# BDL_Eagle.net
KiCad netlist of a schematic drawn in EAGLE
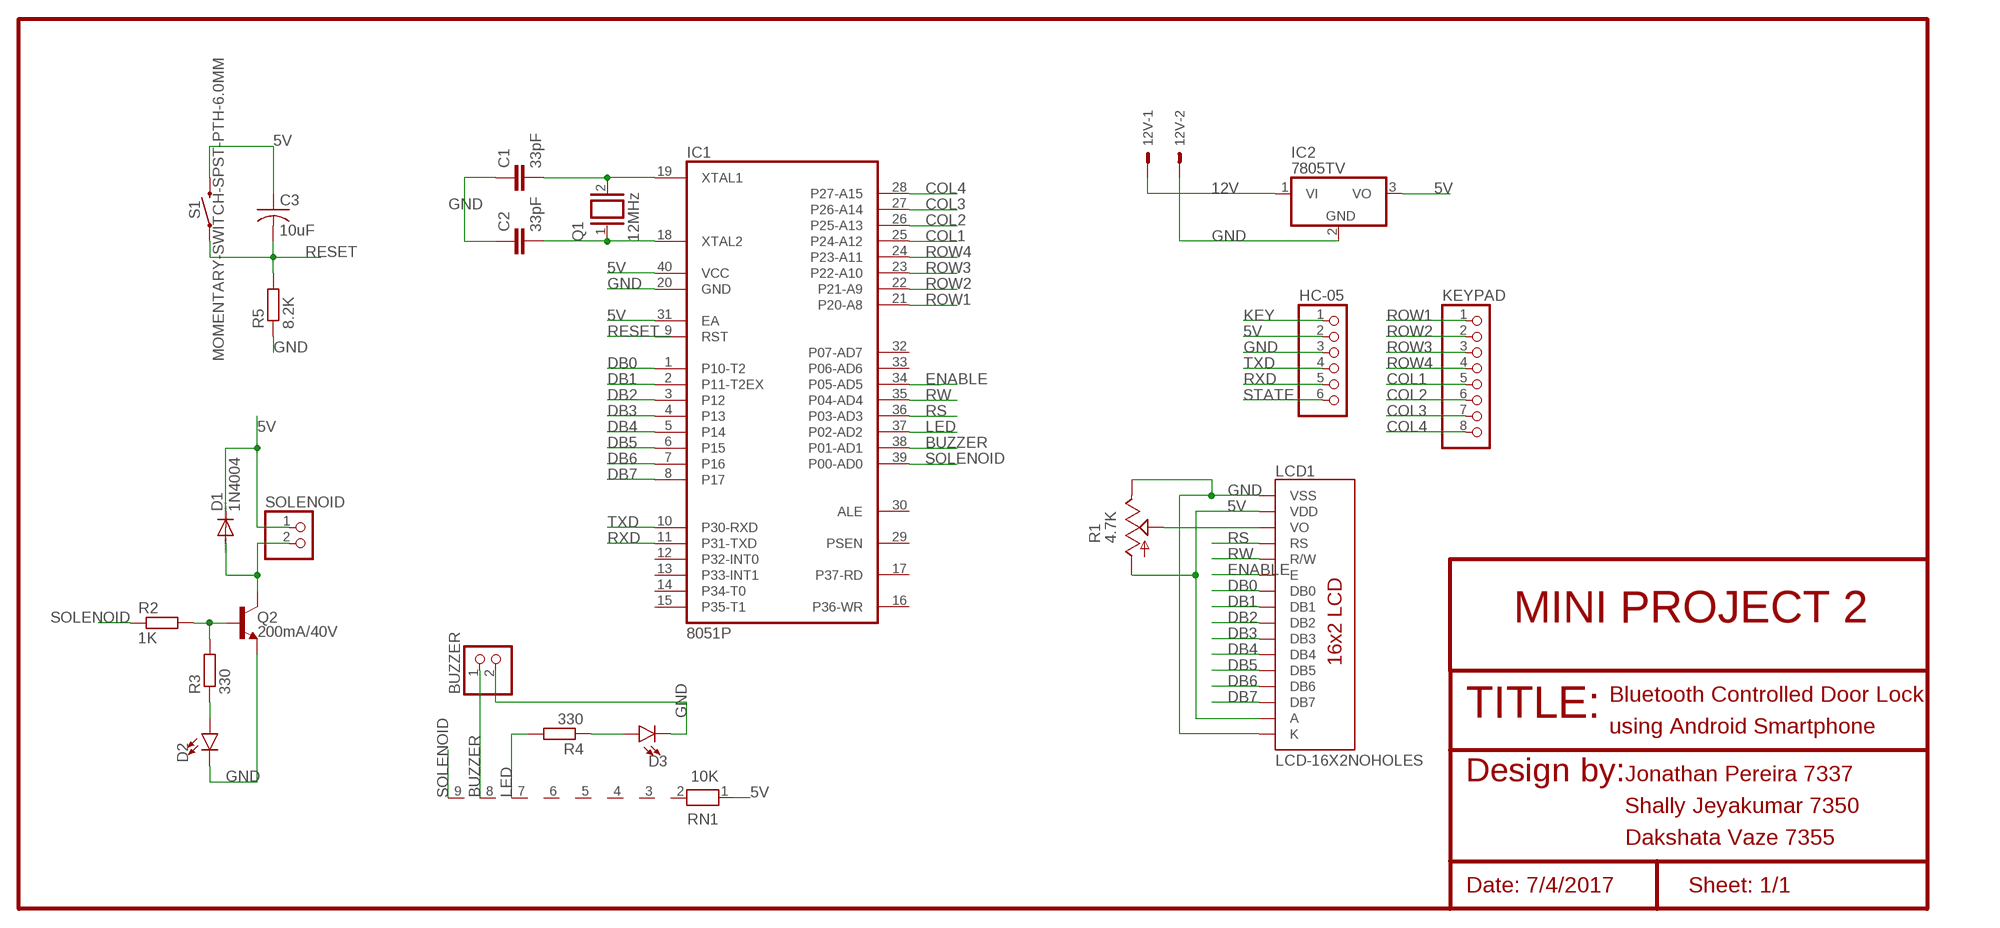
[diagram p0: schematic, sheet 1]

(export (version "E")
  (design (tool "Eeschema 10.0.6"))
  (components
    (comp (ref "12V")
      (value "KK-156-2")
      (footprint "eagle-import:KK-156-2")
      (libsource (lib "eagle-import") (part "KK-156-2"))
    )
    (comp (ref "BUZZER")
      (value "PINHD-1X2")
      (footprint "eagle-import:1X02")
      (libsource (lib "eagle-import") (part "PINHD-1X2"))
    )
    (comp (ref "C1")
      (value "33pF")
      (footprint "eagle-import:C2.5-2")
      (libsource (lib "eagle-import") (part "C2.5/2"))
    )
    (comp (ref "C2")
      (value "33pF")
      (footprint "eagle-import:C2.5-2")
      (libsource (lib "eagle-import") (part "C2.5/2"))
    )
    (comp (ref "C3")
      (value "10uF")
      (footprint "eagle-import:C025-050X050")
      (libsource (lib "eagle-import") (part "C-US025-050X050"))
    )
    (comp (ref "D1")
      (value "1N4004")
      (footprint "eagle-import:DO41-10")
      (libsource (lib "eagle-import") (part "1N4004"))
    )
    (comp (ref "D2")
      (value "LED5MM")
      (footprint "eagle-import:LED_5MM")
      (libsource (lib "eagle-import") (part "LED5MM"))
    )
    (comp (ref "D3")
      (value "LED5MM")
      (footprint "eagle-import:LED_5MM")
      (libsource (lib "eagle-import") (part "LED5MM"))
    )
    (comp (ref "HC-05")
      (value "PINHD-1X6")
      (footprint "eagle-import:1X06")
      (libsource (lib "eagle-import") (part "PINHD-1X6"))
    )
    (comp (ref "IC1")
      (value "8051P")
      (footprint "eagle-import:DIL40")
      (libsource (lib "eagle-import") (part "8051P"))
    )
    (comp (ref "IC2")
      (value "7805TV")
      (footprint "eagle-import:TO220V")
      (libsource (lib "eagle-import") (part "78TV05"))
    )
    (comp (ref "KEYPAD")
      (value "PINHD-1X8")
      (footprint "eagle-import:1X08")
      (libsource (lib "eagle-import") (part "PINHD-1X8"))
    )
    (comp (ref "LCD1")
      (value "LCD-16X2NOHOLES")
      (footprint "eagle-import:LCD-16X2_NOHOLESNOSILK")
      (libsource (lib "eagle-import") (part "LCD-16X2NOHOLES"))
    )
    (comp (ref "Q1")
      (value "12MHz")
      (footprint "eagle-import:QS")
      (libsource (lib "eagle-import") (part "XTAL/S"))
    )
    (comp (ref "Q2")
      (value "200mA/40V")
      (footprint "eagle-import:TO-92-EZ")
      (libsource (lib "eagle-import") (part "TRANS_NPN-2N3904-EZ"))
    )
    (comp (ref "R1")
      (value "4.7K")
      (footprint "eagle-import:CA6V")
      (libsource (lib "eagle-import") (part "TRIM_US-CA6V"))
    )
    (comp (ref "R2")
      (value "1K")
      (footprint "eagle-import:0204_7")
      (libsource (lib "eagle-import") (part "R-EU_0204/7"))
    )
    (comp (ref "R3")
      (value "330")
      (footprint "eagle-import:0204_7")
      (libsource (lib "eagle-import") (part "resistor_R-EU_0204/7"))
    )
    (comp (ref "R4")
      (value "330")
      (footprint "eagle-import:0204_7")
      (libsource (lib "eagle-import") (part "resistor_R-EU_0204/7"))
    )
    (comp (ref "R5")
      (value "8.2K")
      (footprint "eagle-import:0204_7")
      (libsource (lib "eagle-import") (part "resistor_R-EU_0204/7"))
    )
    (comp (ref "RN1")
      (value "10K")
      (footprint "eagle-import:RN-9")
      (libsource (lib "eagle-import") (part "RN08"))
    )
    (comp (ref "S1")
      (value "MOMENTARY-SWITCH-SPST-PTH-6.0MM")
      (footprint "eagle-import:TACTILE_SWITCH_PTH_6.0MM")
      (libsource (lib "eagle-import") (part "MOMENTARY-SWITCH-SPST-PTH-6.0MM"))
    )
    (comp (ref "SOLENOID")
      (value "PINHD-1X2")
      (footprint "eagle-import:1X02")
      (libsource (lib "eagle-import") (part "PINHD-1X2"))
    )
  )
  (nets
    (net (code "1") (name "/5V") (class "Default")
      (node (ref "C3") (pin "1") (pinfunction "1_1") (pintype "passive"))
      (node (ref "D1") (pin "C") (pinfunction "C_C") (pintype "passive"))
      (node (ref "HC-05") (pin "2") (pinfunction "2_2") (pintype "passive"))
      (node (ref "IC1") (pin "31") (pinfunction "EA_31") (pintype "input"))
      (node (ref "IC1") (pin "40") (pinfunction "VCC_40") (pintype "power_in"))
      (node (ref "IC2") (pin "3") (pinfunction "VO_3") (pintype "passive"))
      (node (ref "LCD1") (pin "15") (pinfunction "A_15") (pintype "power_in"))
      (node (ref "LCD1") (pin "2") (pinfunction "VDD_2") (pintype "power_in"))
      (node (ref "R1") (pin "A") (pinfunction "A_A") (pintype "passive"))
      (node (ref "RN1") (pin "1") (pinfunction "1_1") (pintype "passive"))
      (node (ref "S1") (pin "3") (pinfunction "2_3") (pintype "passive"))
      (node (ref "SOLENOID") (pin "1") (pinfunction "1_1") (pintype "passive"))
    )
    (net (code "2") (name "/12V") (class "Default")
      (node (ref "12V") (pin "1") (pinfunction "S_1") (pintype "passive"))
      (node (ref "IC2") (pin "1") (pinfunction "VI_1") (pintype "input"))
    )
    (net (code "3") (name "/BUZZER") (class "Default")
      (node (ref "BUZZER") (pin "1") (pinfunction "1_1") (pintype "passive"))
      (node (ref "IC1") (pin "38") (pinfunction "P01-AD1_38") (pintype "bidirectional"))
      (node (ref "RN1") (pin "8") (pinfunction "8_8") (pintype "passive"))
    )
    (net (code "4") (name "/COL1") (class "Default")
      (node (ref "IC1") (pin "25") (pinfunction "P24-A12_25") (pintype "bidirectional"))
      (node (ref "KEYPAD") (pin "5") (pinfunction "5_5") (pintype "passive"))
    )
    (net (code "5") (name "/COL2") (class "Default")
      (node (ref "IC1") (pin "26") (pinfunction "P25-A13_26") (pintype "bidirectional"))
      (node (ref "KEYPAD") (pin "6") (pinfunction "6_6") (pintype "passive"))
    )
    (net (code "6") (name "/COL3") (class "Default")
      (node (ref "IC1") (pin "27") (pinfunction "P26-A14_27") (pintype "bidirectional"))
      (node (ref "KEYPAD") (pin "7") (pinfunction "7_7") (pintype "passive"))
    )
    (net (code "7") (name "/COL4") (class "Default")
      (node (ref "IC1") (pin "28") (pinfunction "P27-A15_28") (pintype "bidirectional"))
      (node (ref "KEYPAD") (pin "8") (pinfunction "8_8") (pintype "passive"))
    )
    (net (code "8") (name "/DB0") (class "Default")
      (node (ref "IC1") (pin "1") (pinfunction "P10-T2_1") (pintype "bidirectional"))
      (node (ref "LCD1") (pin "7") (pinfunction "DB0_7") (pintype "bidirectional"))
    )
    (net (code "9") (name "/DB1") (class "Default")
      (node (ref "IC1") (pin "2") (pinfunction "P11-T2EX_2") (pintype "bidirectional"))
      (node (ref "LCD1") (pin "8") (pinfunction "DB1_8") (pintype "bidirectional"))
    )
    (net (code "10") (name "/DB2") (class "Default")
      (node (ref "IC1") (pin "3") (pinfunction "P12_3") (pintype "bidirectional"))
      (node (ref "LCD1") (pin "9") (pinfunction "DB2_9") (pintype "bidirectional"))
    )
    (net (code "11") (name "/DB3") (class "Default")
      (node (ref "IC1") (pin "4") (pinfunction "P13_4") (pintype "bidirectional"))
      (node (ref "LCD1") (pin "10") (pinfunction "DB3_10") (pintype "bidirectional"))
    )
    (net (code "12") (name "/DB4") (class "Default")
      (node (ref "IC1") (pin "5") (pinfunction "P14_5") (pintype "bidirectional"))
      (node (ref "LCD1") (pin "11") (pinfunction "DB4_11") (pintype "bidirectional"))
    )
    (net (code "13") (name "/DB5") (class "Default")
      (node (ref "IC1") (pin "6") (pinfunction "P15_6") (pintype "bidirectional"))
      (node (ref "LCD1") (pin "12") (pinfunction "DB5_12") (pintype "bidirectional"))
    )
    (net (code "14") (name "/DB6") (class "Default")
      (node (ref "IC1") (pin "7") (pinfunction "P16_7") (pintype "bidirectional"))
      (node (ref "LCD1") (pin "13") (pinfunction "DB6_13") (pintype "bidirectional"))
    )
    (net (code "15") (name "/DB7") (class "Default")
      (node (ref "IC1") (pin "8") (pinfunction "P17_8") (pintype "bidirectional"))
      (node (ref "LCD1") (pin "14") (pinfunction "DB7_14") (pintype "bidirectional"))
    )
    (net (code "16") (name "/ENABLE") (class "Default")
      (node (ref "IC1") (pin "34") (pinfunction "P05-AD5_34") (pintype "bidirectional"))
      (node (ref "LCD1") (pin "6") (pinfunction "E_6") (pintype "input"))
    )
    (net (code "17") (name "/GND") (class "Default")
      (node (ref "12V") (pin "2") (pinfunction "S_2") (pintype "passive"))
      (node (ref "BUZZER") (pin "2") (pinfunction "2_2") (pintype "passive"))
      (node (ref "C1") (pin "1") (pinfunction "1_1") (pintype "passive"))
      (node (ref "C2") (pin "1") (pinfunction "1_1") (pintype "passive"))
      (node (ref "D2") (pin "K") (pinfunction "C_K") (pintype "passive"))
      (node (ref "D3") (pin "K") (pinfunction "C_K") (pintype "passive"))
      (node (ref "HC-05") (pin "3") (pinfunction "3_3") (pintype "passive"))
      (node (ref "IC1") (pin "20") (pinfunction "GND_20") (pintype "power_in"))
      (node (ref "IC2") (pin "2") (pinfunction "GND_2") (pintype "passive"))
      (node (ref "LCD1") (pin "1") (pinfunction "VSS_1") (pintype "power_in"))
      (node (ref "LCD1") (pin "16") (pinfunction "K_16") (pintype "power_in"))
      (node (ref "Q2") (pin "1") (pinfunction "E_1") (pintype "passive"))
      (node (ref "R1") (pin "E") (pinfunction "E_E") (pintype "passive"))
      (node (ref "R5") (pin "1") (pinfunction "1_1") (pintype "passive"))
    )
    (net (code "18") (name "/KEY") (class "Default")
      (node (ref "HC-05") (pin "1") (pinfunction "1_1") (pintype "passive"))
    )
    (net (code "19") (name "/LED") (class "Default")
      (node (ref "IC1") (pin "37") (pinfunction "P02-AD2_37") (pintype "bidirectional"))
      (node (ref "R4") (pin "2") (pinfunction "2_2") (pintype "passive"))
      (node (ref "RN1") (pin "7") (pinfunction "7_7") (pintype "passive"))
    )
    (net (code "20") (name "/RESET") (class "Default")
      (node (ref "C3") (pin "2") (pinfunction "2_2") (pintype "passive"))
      (node (ref "R5") (pin "2") (pinfunction "2_2") (pintype "passive"))
      (node (ref "S1") (pin "1") (pinfunction "1_1") (pintype "passive"))
    )
    (net (code "21") (name "/ROW1") (class "Default")
      (node (ref "IC1") (pin "21") (pinfunction "P20-A8_21") (pintype "bidirectional"))
      (node (ref "KEYPAD") (pin "1") (pinfunction "1_1") (pintype "passive"))
    )
    (net (code "22") (name "/ROW2") (class "Default")
      (node (ref "IC1") (pin "22") (pinfunction "P21-A9_22") (pintype "bidirectional"))
      (node (ref "KEYPAD") (pin "2") (pinfunction "2_2") (pintype "passive"))
    )
    (net (code "23") (name "/ROW3") (class "Default")
      (node (ref "IC1") (pin "23") (pinfunction "P22-A10_23") (pintype "bidirectional"))
      (node (ref "KEYPAD") (pin "3") (pinfunction "3_3") (pintype "passive"))
    )
    (net (code "24") (name "/ROW4") (class "Default")
      (node (ref "IC1") (pin "24") (pinfunction "P23-A11_24") (pintype "bidirectional"))
      (node (ref "KEYPAD") (pin "4") (pinfunction "4_4") (pintype "passive"))
    )
    (net (code "25") (name "/RS") (class "Default")
      (node (ref "IC1") (pin "36") (pinfunction "P03-AD3_36") (pintype "bidirectional"))
      (node (ref "LCD1") (pin "4") (pinfunction "RS_4") (pintype "input"))
    )
    (net (code "26") (name "/RW") (class "Default")
      (node (ref "IC1") (pin "35") (pinfunction "P04-AD4_35") (pintype "bidirectional"))
      (node (ref "LCD1") (pin "5") (pinfunction "R/W_5") (pintype "input"))
    )
    (net (code "27") (name "/RXD") (class "Default")
      (node (ref "HC-05") (pin "5") (pinfunction "5_5") (pintype "passive"))
      (node (ref "IC1") (pin "11") (pinfunction "P31-TXD_11") (pintype "bidirectional"))
    )
    (net (code "28") (name "/SOLENOID") (class "Default")
      (node (ref "IC1") (pin "39") (pinfunction "P00-AD0_39") (pintype "bidirectional"))
      (node (ref "R2") (pin "1") (pinfunction "1_1") (pintype "passive"))
      (node (ref "RN1") (pin "9") (pinfunction "9_9") (pintype "passive"))
    )
    (net (code "29") (name "/STATE") (class "Default")
      (node (ref "HC-05") (pin "6") (pinfunction "6_6") (pintype "passive"))
    )
    (net (code "30") (name "/TXD") (class "Default")
      (node (ref "HC-05") (pin "4") (pinfunction "4_4") (pintype "passive"))
      (node (ref "IC1") (pin "10") (pinfunction "P30-RXD_10") (pintype "bidirectional"))
    )
    (net (code "31") (name "Net-(D2-PadA)") (class "Default")
      (node (ref "D2") (pin "A") (pinfunction "A_A") (pintype "passive"))
      (node (ref "R3") (pin "1") (pinfunction "1_1") (pintype "passive"))
    )
    (net (code "32") (name "Net-(D3-PadA)") (class "Default")
      (node (ref "D3") (pin "A") (pinfunction "A_A") (pintype "passive"))
      (node (ref "R4") (pin "1") (pinfunction "1_1") (pintype "passive"))
    )
    (net (code "33") (name "Net-(IC1-XTAL1)") (class "Default")
      (node (ref "C1") (pin "2") (pinfunction "2_2") (pintype "passive"))
      (node (ref "IC1") (pin "19") (pinfunction "XTAL1_19") (pintype "input"))
      (node (ref "Q1") (pin "2") (pinfunction "2_2") (pintype "passive"))
    )
    (net (code "34") (name "Net-(IC1-XTAL2)") (class "Default")
      (node (ref "C2") (pin "2") (pinfunction "2_2") (pintype "passive"))
      (node (ref "IC1") (pin "18") (pinfunction "XTAL2_18") (pintype "input"))
      (node (ref "Q1") (pin "1") (pinfunction "1_1") (pintype "passive"))
    )
    (net (code "35") (name "Net-(LCD1-VO)") (class "Default")
      (node (ref "LCD1") (pin "3") (pinfunction "VO_3") (pintype "bidirectional"))
      (node (ref "R1") (pin "S") (pinfunction "S_S") (pintype "passive"))
    )
    (net (code "36") (name "Net-(Q2-B)") (class "Default")
      (node (ref "Q2") (pin "2") (pinfunction "B_2") (pintype "passive"))
      (node (ref "R2") (pin "2") (pinfunction "2_2") (pintype "passive"))
      (node (ref "R3") (pin "2") (pinfunction "2_2") (pintype "passive"))
    )
    (net (code "37") (name "Net-(Q2-C)") (class "Default")
      (node (ref "D1") (pin "A") (pinfunction "A_A") (pintype "passive"))
      (node (ref "Q2") (pin "3") (pinfunction "C_3") (pintype "passive"))
      (node (ref "SOLENOID") (pin "2") (pinfunction "2_2") (pintype "passive"))
    )
    (net (code "38") (name "unconnected-(IC1-ALE-Pad30)") (class "Default")
      (node (ref "IC1") (pin "30") (pinfunction "ALE_30") (pintype "output"))
    )
    (net (code "39") (name "unconnected-(IC1-P06-AD6-Pad33)") (class "Default")
      (node (ref "IC1") (pin "33") (pinfunction "P06-AD6_33") (pintype "bidirectional"))
    )
    (net (code "40") (name "unconnected-(IC1-P07-AD7-Pad32)") (class "Default")
      (node (ref "IC1") (pin "32") (pinfunction "P07-AD7_32") (pintype "bidirectional"))
    )
    (net (code "41") (name "unconnected-(IC1-P32-INT0-Pad12)") (class "Default")
      (node (ref "IC1") (pin "12") (pinfunction "P32-INT0_12") (pintype "bidirectional"))
    )
    (net (code "42") (name "unconnected-(IC1-P33-INT1-Pad13)") (class "Default")
      (node (ref "IC1") (pin "13") (pinfunction "P33-INT1_13") (pintype "bidirectional"))
    )
    (net (code "43") (name "unconnected-(IC1-P34-T0-Pad14)") (class "Default")
      (node (ref "IC1") (pin "14") (pinfunction "P34-T0_14") (pintype "bidirectional"))
    )
    (net (code "44") (name "unconnected-(IC1-P35-T1-Pad15)") (class "Default")
      (node (ref "IC1") (pin "15") (pinfunction "P35-T1_15") (pintype "bidirectional"))
    )
    (net (code "45") (name "unconnected-(IC1-P36-WR-Pad16)") (class "Default")
      (node (ref "IC1") (pin "16") (pinfunction "P36-WR_16") (pintype "bidirectional"))
    )
    (net (code "46") (name "unconnected-(IC1-P37-RD-Pad17)") (class "Default")
      (node (ref "IC1") (pin "17") (pinfunction "P37-RD_17") (pintype "bidirectional"))
    )
    (net (code "47") (name "unconnected-(IC1-PSEN-Pad29)") (class "Default")
      (node (ref "IC1") (pin "29") (pinfunction "PSEN_29") (pintype "output"))
    )
    (net (code "48") (name "unconnected-(IC1-RST-Pad9)") (class "Default")
      (node (ref "IC1") (pin "9") (pinfunction "RST_9") (pintype "input"))
    )
    (net (code "49") (name "unconnected-(RN1-Pad2)") (class "Default")
      (node (ref "RN1") (pin "2") (pinfunction "2_2") (pintype "passive"))
    )
    (net (code "50") (name "unconnected-(RN1-Pad3)") (class "Default")
      (node (ref "RN1") (pin "3") (pinfunction "3_3") (pintype "passive"))
    )
    (net (code "51") (name "unconnected-(RN1-Pad4)") (class "Default")
      (node (ref "RN1") (pin "4") (pinfunction "4_4") (pintype "passive"))
    )
    (net (code "52") (name "unconnected-(RN1-Pad5)") (class "Default")
      (node (ref "RN1") (pin "5") (pinfunction "5_5") (pintype "passive"))
    )
    (net (code "53") (name "unconnected-(RN1-Pad6)") (class "Default")
      (node (ref "RN1") (pin "6") (pinfunction "6_6") (pintype "passive"))
    )
  )
)
